# LedRYG.net
KiCad netlist of a schematic drawn in Altium Designer
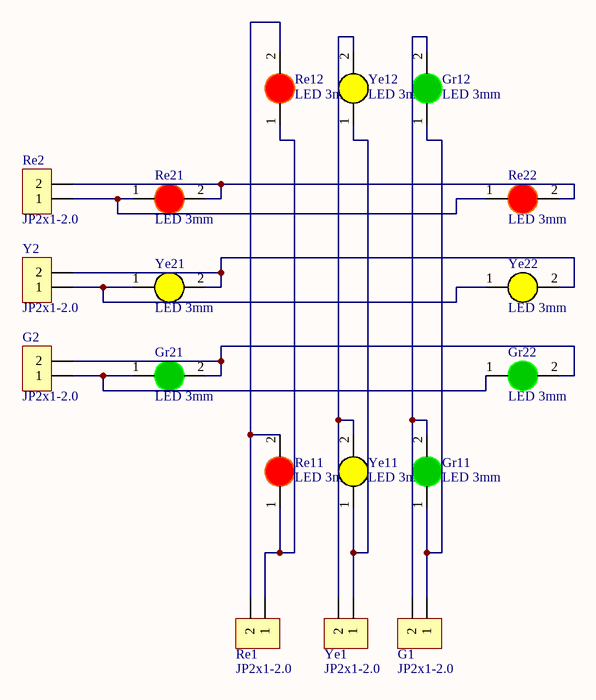
[diagram p0: LedRYG.SchDoc]

(export (version "E")
  (design (tool "Eeschema 10.0.6"))
  (components
    (comp (ref "G1")
      (value "JP2x1-2.0")
      (footprint "J2-C1T")
      (description "WR-PHD 2.00 mm Socket Header")
      (fields
        (field (name "MANUFACTURER") "Würth Elektronik eiSos GmbH")
        (field (name "PARTNO") "62000211821")
        (field (name "CREATED BY") "Karrer Zheng")
      )
      (libsource (lib "") (part "JP2x1-2.0_1"))
    )
    (comp (ref "G2")
      (value "JP2x1-2.0")
      (footprint "J2-C1T")
      (description "WR-PHD 2.00 mm Socket Header")
      (fields
        (field (name "MANUFACTURER") "Würth Elektronik eiSos GmbH")
        (field (name "PARTNO") "62000211821")
        (field (name "CREATED BY") "Karrer Zheng")
      )
      (libsource (lib "control_traffic") (part "JP2x1-2.0"))
    )
    (comp (ref "Gr11")
      (value "LED 3mm")
      (footprint "LED-3MM-GREEN")
      (description "Cắm")
      (libsource (lib "Altium_Lib_by_KhueNguyenCreator") (part "LED 3mm Xanh La"))
    )
    (comp (ref "Gr12")
      (value "LED 3mm")
      (footprint "LED-3MM-GREEN")
      (description "Cắm")
      (libsource (lib "Altium_Lib_by_KhueNguyenCreator") (part "LED 3mm Xanh La"))
    )
    (comp (ref "Gr21")
      (value "LED 3mm")
      (footprint "LED-3MM-GREEN")
      (description "Cắm")
      (libsource (lib "Altium_Lib_by_KhueNguyenCreator") (part "LED 3mm Xanh La"))
    )
    (comp (ref "Gr22")
      (value "LED 3mm")
      (footprint "LED-3MM-GREEN")
      (description "Cắm")
      (libsource (lib "Altium_Lib_by_KhueNguyenCreator") (part "LED 3mm Xanh La"))
    )
    (comp (ref "Re1")
      (value "JP2x1-2.0")
      (footprint "J2-C1T")
      (description "WR-PHD 2.00 mm Socket Header")
      (fields
        (field (name "MANUFACTURER") "Würth Elektronik eiSos GmbH")
        (field (name "PARTNO") "62000211821")
        (field (name "CREATED BY") "Karrer Zheng")
      )
      (libsource (lib "") (part "JP2x1-2.0_1"))
    )
    (comp (ref "Re2")
      (value "JP2x1-2.0")
      (footprint "J2-C1T")
      (description "WR-PHD 2.00 mm Socket Header")
      (fields
        (field (name "MANUFACTURER") "Würth Elektronik eiSos GmbH")
        (field (name "PARTNO") "62000211821")
        (field (name "CREATED BY") "Karrer Zheng")
      )
      (libsource (lib "control_traffic") (part "JP2x1-2.0"))
    )
    (comp (ref "Re11")
      (value "LED 3mm")
      (footprint "LED-3MM-RED")
      (description "Cắm")
      (libsource (lib "Altium_Lib_by_KhueNguyenCreator") (part "LED 3mm Do"))
    )
    (comp (ref "Re12")
      (value "LED 3mm")
      (footprint "LED-3MM-RED")
      (description "Cắm")
      (libsource (lib "Altium_Lib_by_KhueNguyenCreator") (part "LED 3mm Do"))
    )
    (comp (ref "Re21")
      (value "LED 3mm")
      (footprint "LED-3MM-RED")
      (description "Cắm")
      (libsource (lib "Altium_Lib_by_KhueNguyenCreator") (part "LED 3mm Do"))
    )
    (comp (ref "Re22")
      (value "LED 3mm")
      (footprint "LED-3MM-RED")
      (description "Cắm")
      (libsource (lib "Altium_Lib_by_KhueNguyenCreator") (part "LED 3mm Do"))
    )
    (comp (ref "Y2")
      (value "JP2x1-2.0")
      (footprint "J2-C1T")
      (description "WR-PHD 2.00 mm Socket Header")
      (fields
        (field (name "MANUFACTURER") "Würth Elektronik eiSos GmbH")
        (field (name "PARTNO") "62000211821")
        (field (name "CREATED BY") "Karrer Zheng")
      )
      (libsource (lib "control_traffic") (part "JP2x1-2.0"))
    )
    (comp (ref "Ye1")
      (value "JP2x1-2.0")
      (footprint "J2-C1T")
      (description "WR-PHD 2.00 mm Socket Header")
      (fields
        (field (name "MANUFACTURER") "Würth Elektronik eiSos GmbH")
        (field (name "PARTNO") "62000211821")
        (field (name "CREATED BY") "Karrer Zheng")
      )
      (libsource (lib "") (part "JP2x1-2.0_1"))
    )
    (comp (ref "Ye11")
      (value "LED 3mm")
      (footprint "LED-3MM-YELLOW")
      (description "Cắm")
      (libsource (lib "Altium_Lib_by_KhueNguyenCreator") (part "LED 3mm Vang"))
    )
    (comp (ref "Ye12")
      (value "LED 3mm")
      (footprint "LED-3MM-YELLOW")
      (description "Cắm")
      (libsource (lib "Altium_Lib_by_KhueNguyenCreator") (part "LED 3mm Vang"))
    )
    (comp (ref "Ye21")
      (value "LED 3mm")
      (footprint "LED-3MM-YELLOW")
      (description "Cắm")
      (libsource (lib "Altium_Lib_by_KhueNguyenCreator") (part "LED 3mm Vang"))
    )
    (comp (ref "Ye22")
      (value "LED 3mm")
      (footprint "LED-3MM-YELLOW")
      (description "Cắm")
      (libsource (lib "Altium_Lib_by_KhueNguyenCreator") (part "LED 3mm Vang"))
    )
  )
  (nets
    (net (code "1") (name "Net-(Gr11-A)") (class "Default")
      (node (ref "G1") (pin "1") (pinfunction "1_1") (pintype "passive"))
      (node (ref "Gr11") (pin "1") (pinfunction "A_1") (pintype "passive"))
      (node (ref "Gr12") (pin "1") (pinfunction "A_1") (pintype "passive"))
    )
    (net (code "2") (name "Net-(Gr11-K)") (class "Default")
      (node (ref "G1") (pin "2") (pinfunction "2_2") (pintype "passive"))
      (node (ref "Gr11") (pin "2") (pinfunction "K_2") (pintype "passive"))
      (node (ref "Gr12") (pin "2") (pinfunction "K_2") (pintype "passive"))
    )
    (net (code "3") (name "Net-(Gr21-A)") (class "Default")
      (node (ref "G2") (pin "1") (pinfunction "1_1") (pintype "passive"))
      (node (ref "Gr21") (pin "1") (pinfunction "A_1") (pintype "passive"))
      (node (ref "Gr22") (pin "1") (pinfunction "A_1") (pintype "passive"))
    )
    (net (code "4") (name "Net-(Gr21-K)") (class "Default")
      (node (ref "G2") (pin "2") (pinfunction "2_2") (pintype "passive"))
      (node (ref "Gr21") (pin "2") (pinfunction "K_2") (pintype "passive"))
      (node (ref "Gr22") (pin "2") (pinfunction "K_2") (pintype "passive"))
    )
    (net (code "5") (name "Net-(Re11-A)") (class "Default")
      (node (ref "Re1") (pin "1") (pinfunction "1_1") (pintype "passive"))
      (node (ref "Re11") (pin "1") (pinfunction "A_1") (pintype "passive"))
      (node (ref "Re12") (pin "1") (pinfunction "A_1") (pintype "passive"))
    )
    (net (code "6") (name "Net-(Re11-K)") (class "Default")
      (node (ref "Re1") (pin "2") (pinfunction "2_2") (pintype "passive"))
      (node (ref "Re11") (pin "2") (pinfunction "K_2") (pintype "passive"))
      (node (ref "Re12") (pin "2") (pinfunction "K_2") (pintype "passive"))
    )
    (net (code "7") (name "Net-(Re21-A)") (class "Default")
      (node (ref "Re2") (pin "1") (pinfunction "1_1") (pintype "passive"))
      (node (ref "Re21") (pin "1") (pinfunction "A_1") (pintype "passive"))
      (node (ref "Re22") (pin "1") (pinfunction "A_1") (pintype "passive"))
    )
    (net (code "8") (name "Net-(Re21-K)") (class "Default")
      (node (ref "Re2") (pin "2") (pinfunction "2_2") (pintype "passive"))
      (node (ref "Re21") (pin "2") (pinfunction "K_2") (pintype "passive"))
      (node (ref "Re22") (pin "2") (pinfunction "K_2") (pintype "passive"))
    )
    (net (code "9") (name "Net-(Ye11-A)") (class "Default")
      (node (ref "Ye1") (pin "1") (pinfunction "1_1") (pintype "passive"))
      (node (ref "Ye11") (pin "1") (pinfunction "A_1") (pintype "passive"))
      (node (ref "Ye12") (pin "1") (pinfunction "A_1") (pintype "passive"))
    )
    (net (code "10") (name "Net-(Ye11-K)") (class "Default")
      (node (ref "Ye1") (pin "2") (pinfunction "2_2") (pintype "passive"))
      (node (ref "Ye11") (pin "2") (pinfunction "K_2") (pintype "passive"))
      (node (ref "Ye12") (pin "2") (pinfunction "K_2") (pintype "passive"))
    )
    (net (code "11") (name "Net-(Ye21-A)") (class "Default")
      (node (ref "Y2") (pin "1") (pinfunction "1_1") (pintype "passive"))
      (node (ref "Ye21") (pin "1") (pinfunction "A_1") (pintype "passive"))
      (node (ref "Ye22") (pin "1") (pinfunction "A_1") (pintype "passive"))
    )
    (net (code "12") (name "Net-(Ye21-K)") (class "Default")
      (node (ref "Y2") (pin "2") (pinfunction "2_2") (pintype "passive"))
      (node (ref "Ye21") (pin "2") (pinfunction "K_2") (pintype "passive"))
      (node (ref "Ye22") (pin "2") (pinfunction "K_2") (pintype "passive"))
    )
  )
)
